# Tag_V1.net
KiCad netlist of a schematic drawn in EAGLE
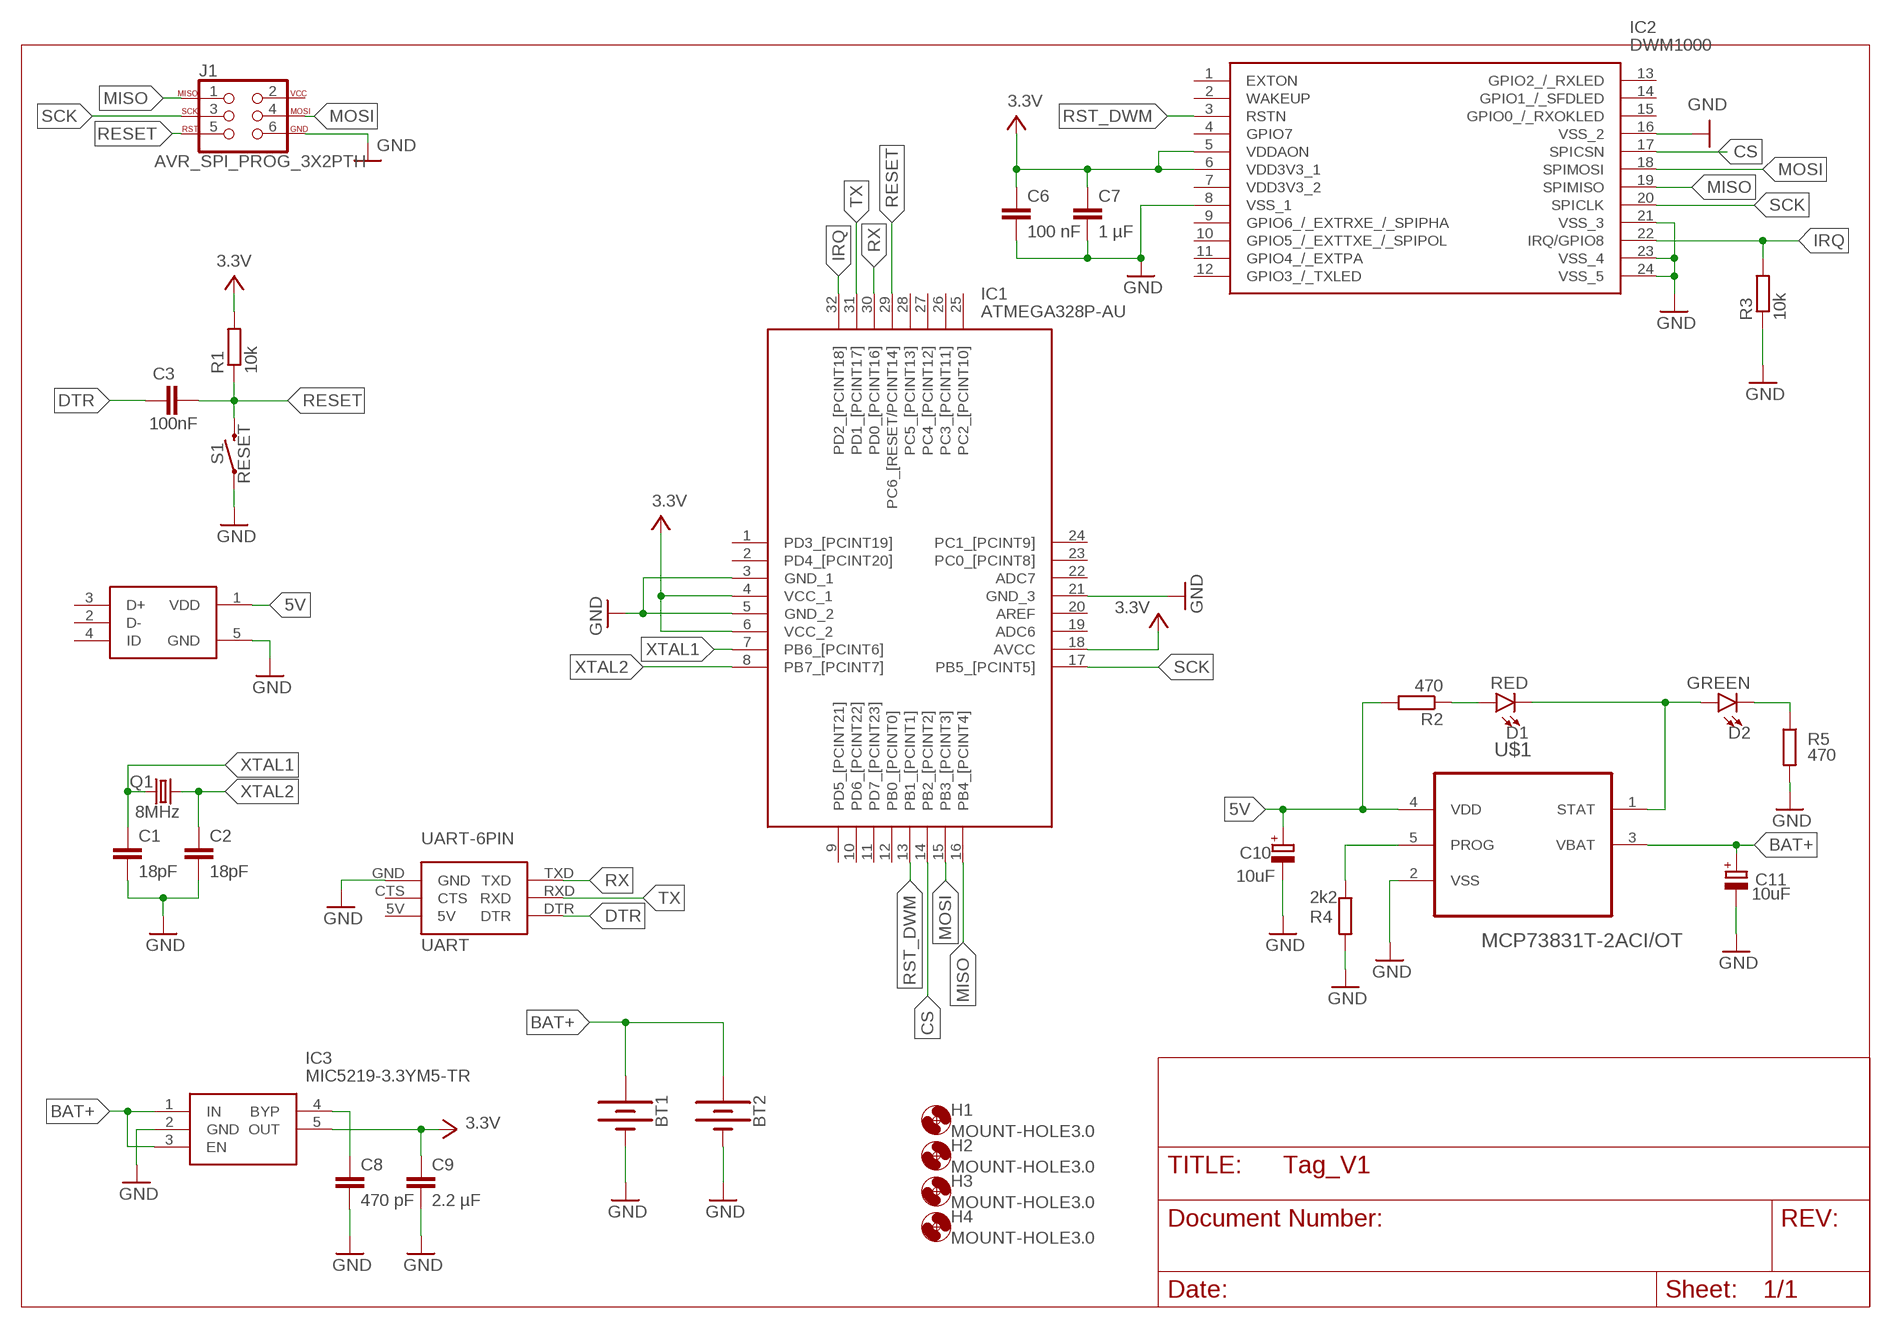
[diagram p0: schematic, sheet 1]

(export (version "E")
  (design (tool "Eeschema 10.0.6"))
  (components
    (comp (ref "BT1")
      (value "BATTERY-18650")
      (footprint "eagle-import:BATTERY_18650-HOLDER")
      (libsource (lib "eagle-import") (part "BATTERY-18650"))
    )
    (comp (ref "BT2")
      (value "BATTERY-18650")
      (footprint "eagle-import:BATTERY_18650-HOLDER")
      (libsource (lib "eagle-import") (part "BATTERY-18650"))
    )
    (comp (ref "C1")
      (value "18pF")
      (footprint "eagle-import:C0805")
      (libsource (lib "eagle-import") (part "C-EUC0805"))
    )
    (comp (ref "C2")
      (value "18pF")
      (footprint "eagle-import:C0805")
      (libsource (lib "eagle-import") (part "C-EUC0805"))
    )
    (comp (ref "C3")
      (value "100nF")
      (footprint "eagle-import:C0805")
      (libsource (lib "eagle-import") (part "C-EUC0805"))
    )
    (comp (ref "C6")
      (value "100 nF")
      (footprint "eagle-import:C0805")
      (libsource (lib "eagle-import") (part "C-EUC0805"))
    )
    (comp (ref "C7")
      (value "1 µF")
      (footprint "eagle-import:C0805")
      (libsource (lib "eagle-import") (part "C-EUC0805"))
    )
    (comp (ref "C8")
      (value "470 pF")
      (footprint "eagle-import:C0805")
      (libsource (lib "eagle-import") (part "C-EUC0805"))
    )
    (comp (ref "C9")
      (value "2.2 µF")
      (footprint "eagle-import:C0805")
      (libsource (lib "eagle-import") (part "C-EUC0805"))
    )
    (comp (ref "C10")
      (value "10uF")
      (footprint "eagle-import:E2,5-7")
      (libsource (lib "eagle-import") (part "CPOL-EUE2.5-7"))
    )
    (comp (ref "C11")
      (value "10uF")
      (footprint "eagle-import:E2,5-7")
      (libsource (lib "eagle-import") (part "CPOL-EUE2.5-7"))
    )
    (comp (ref "D1")
      (value "RED")
      (footprint "eagle-import:LED-1206")
      (libsource (lib "eagle-import") (part "LED-RED1206"))
    )
    (comp (ref "D2")
      (value "GREEN")
      (footprint "eagle-import:LED-1206")
      (libsource (lib "eagle-import") (part "LED-GREEN1206"))
    )
    (comp (ref "H1")
      (value "MOUNT-HOLE3.0")
      (footprint "eagle-import:3,0")
      (libsource (lib "eagle-import") (part "MOUNT-HOLE3.0"))
    )
    (comp (ref "H2")
      (value "MOUNT-HOLE3.0")
      (footprint "eagle-import:3,0")
      (libsource (lib "eagle-import") (part "MOUNT-HOLE3.0"))
    )
    (comp (ref "H3")
      (value "MOUNT-HOLE3.0")
      (footprint "eagle-import:3,0")
      (libsource (lib "eagle-import") (part "MOUNT-HOLE3.0"))
    )
    (comp (ref "H4")
      (value "MOUNT-HOLE3.0")
      (footprint "eagle-import:3,0")
      (libsource (lib "eagle-import") (part "MOUNT-HOLE3.0"))
    )
    (comp (ref "IC1")
      (value "ATMEGA328P-AU")
      (footprint "eagle-import:QFP80P900X900X120-32N")
      (fields (field (name "RS_PART_NUMBER") "1310271"))
      (libsource (lib "eagle-import") (part "ATMEGA328P-AU"))
    )
    (comp (ref "IC2")
      (value "DWM1000")
      (footprint "eagle-import:DWM1000")
      (libsource (lib "eagle-import") (part "DWM1000"))
    )
    (comp (ref "IC3")
      (value "MIC5219-3.3YM5-TR")
      (footprint "eagle-import:SOT95P280X130-5N")
      (fields
        (field (name "MOUSER_PART_NUMBER") "998-MIC5219-3.3YM5TR")
        (field (name "RS_PART_NUMBER") "9101685P")
      )
      (libsource (lib "eagle-import") (part "MIC5219-3.3YM5-TR"))
    )
    (comp (ref "J1")
      (value "AVR_SPI_PROG_3X2PTH")
      (footprint "eagle-import:2X3")
      (libsource (lib "eagle-import") (part "AVR_SPI_PROG_3X2PTH"))
    )
    (comp (ref "Q1")
      (value "8MHz")
      (footprint "eagle-import:HC49UP")
      (libsource (lib "eagle-import") (part "CRYSTALHC49UP"))
    )
    (comp (ref "R1")
      (value "10k")
      (footprint "eagle-import:R0805")
      (libsource (lib "eagle-import") (part "R-EU_R0805"))
    )
    (comp (ref "R2")
      (value "470")
      (footprint "eagle-import:R0805")
      (libsource (lib "eagle-import") (part "R-EU_R0805"))
    )
    (comp (ref "R3")
      (value "10k")
      (footprint "eagle-import:R0805")
      (libsource (lib "eagle-import") (part "R-EU_R0805"))
    )
    (comp (ref "R4")
      (value "2k2")
      (footprint "eagle-import:R0805")
      (libsource (lib "eagle-import") (part "R-EU_R0805"))
    )
    (comp (ref "R5")
      (value "470")
      (footprint "eagle-import:R0805")
      (libsource (lib "eagle-import") (part "R-EU_R0805"))
    )
    (comp (ref "S1")
      (value "RESET")
      (footprint "eagle-import:TACTILE_SWITCH_PTH_6.0MM")
      (libsource (lib "eagle-import") (part "MOMENTARY-SWITCH-SPST-PTH-6.0MM"))
    )
    (comp (ref "U$1")
      (value "MCP73831T-2ACI/OT")
      (footprint "eagle-import:SOT95P280X145-5N")
      (fields (field (name "MF") "Microchip"))
      (libsource (lib "eagle-import") (part "MCP73831T-2ACI/OT"))
    )
    (comp (ref "U$2")
      (value "UART-6PIN")
      (footprint "eagle-import:UART-6PIN")
      (libsource (lib "eagle-import") (part "UART-6PIN"))
    )
    (comp (ref "U1")
      (value "105017-0001")
      (footprint "eagle-import:MOLEX_105017-0001")
      (fields (field (name "MF") "Molex"))
      (libsource (lib "eagle-import") (part "105017-0001"))
    )
  )
  (nets
    (net (code "1") (name "5V") (class "Default")
      (node (ref "C10") (pin "+") (pinfunction "+_+") (pintype "passive"))
      (node (ref "R2") (pin "2") (pinfunction "2_2") (pintype "passive"))
      (node (ref "U$1") (pin "4") (pinfunction "VDD_4") (pintype "power_in"))
      (node (ref "U1") (pin "1") (pinfunction "VDD_1") (pintype "power_in"))
    )
    (net (code "2") (name "BAT+") (class "Default")
      (node (ref "BT1") (pin "PWR@1") (pinfunction "+_PWR@1") (pintype "power_in"))
      (node (ref "BT2") (pin "PWR@1") (pinfunction "+_PWR@1") (pintype "power_in"))
      (node (ref "C11") (pin "+") (pinfunction "+_+") (pintype "passive"))
      (node (ref "IC3") (pin "1") (pinfunction "IN_1") (pintype "bidirectional"))
      (node (ref "IC3") (pin "3") (pinfunction "EN_3") (pintype "bidirectional"))
      (node (ref "U$1") (pin "3") (pinfunction "VBAT_3") (pintype "output"))
    )
    (net (code "3") (name "CS") (class "Default")
      (node (ref "IC1") (pin "14") (pinfunction "PB2_[PCINT2]_14") (pintype "bidirectional"))
      (node (ref "IC2") (pin "17") (pinfunction "SPICSN_17") (pintype "bidirectional"))
    )
    (net (code "4") (name "DTR") (class "Default")
      (node (ref "C3") (pin "1") (pinfunction "1_1") (pintype "passive"))
      (node (ref "U$2") (pin "DTR") (pinfunction "DTR_DTR") (pintype "bidirectional"))
    )
    (net (code "5") (name "GND") (class "Default")
      (node (ref "BT1") (pin "GND@1") (pinfunction "-_GND@1") (pintype "power_in"))
      (node (ref "BT2") (pin "GND@1") (pinfunction "-_GND@1") (pintype "power_in"))
      (node (ref "C1") (pin "2") (pinfunction "2_2") (pintype "passive"))
      (node (ref "C10") (pin "-") (pinfunction "-_-") (pintype "passive"))
      (node (ref "C11") (pin "-") (pinfunction "-_-") (pintype "passive"))
      (node (ref "C2") (pin "2") (pinfunction "2_2") (pintype "passive"))
      (node (ref "C6") (pin "2") (pinfunction "2_2") (pintype "passive"))
      (node (ref "C7") (pin "2") (pinfunction "2_2") (pintype "passive"))
      (node (ref "C8") (pin "2") (pinfunction "2_2") (pintype "passive"))
      (node (ref "C9") (pin "2") (pinfunction "2_2") (pintype "passive"))
      (node (ref "IC1") (pin "21") (pinfunction "GND_3_21") (pintype "power_in"))
      (node (ref "IC1") (pin "3") (pinfunction "GND_1_3") (pintype "power_in"))
      (node (ref "IC1") (pin "5") (pinfunction "GND_2_5") (pintype "power_in"))
      (node (ref "IC2") (pin "16") (pinfunction "VSS_2_16") (pintype "bidirectional"))
      (node (ref "IC2") (pin "21") (pinfunction "VSS_3_21") (pintype "bidirectional"))
      (node (ref "IC2") (pin "23") (pinfunction "VSS_4_23") (pintype "bidirectional"))
      (node (ref "IC2") (pin "24") (pinfunction "VSS_5_24") (pintype "bidirectional"))
      (node (ref "IC2") (pin "8") (pinfunction "VSS_1_8") (pintype "bidirectional"))
      (node (ref "IC3") (pin "2") (pinfunction "GND_2") (pintype "bidirectional"))
      (node (ref "J1") (pin "6") (pinfunction "6_6") (pintype "passive"))
      (node (ref "R3") (pin "1") (pinfunction "1_1") (pintype "passive"))
      (node (ref "R4") (pin "2") (pinfunction "2_2") (pintype "passive"))
      (node (ref "R5") (pin "2") (pinfunction "2_2") (pintype "passive"))
      (node (ref "S1") (pin "1") (pinfunction "1_1") (pintype "passive"))
      (node (ref "U$1") (pin "2") (pinfunction "VSS_2") (pintype "power_in"))
      (node (ref "U$2") (pin "GND") (pinfunction "GND_GND") (pintype "bidirectional"))
      (node (ref "U1") (pin "5") (pinfunction "GND_5") (pintype "power_in"))
    )
    (net (code "6") (name "IRQ") (class "Default")
      (node (ref "IC1") (pin "32") (pinfunction "PD2_[PCINT18]_32") (pintype "bidirectional"))
      (node (ref "IC2") (pin "22") (pinfunction "IRQ/GPIO8_22") (pintype "bidirectional"))
      (node (ref "R3") (pin "2") (pinfunction "2_2") (pintype "passive"))
    )
    (net (code "7") (name "MISO") (class "Default")
      (node (ref "IC1") (pin "16") (pinfunction "PB4_[PCINT4]_16") (pintype "bidirectional"))
      (node (ref "IC2") (pin "19") (pinfunction "SPIMISO_19") (pintype "bidirectional"))
      (node (ref "J1") (pin "1") (pinfunction "1_1") (pintype "passive"))
    )
    (net (code "8") (name "MOSI") (class "Default")
      (node (ref "IC1") (pin "15") (pinfunction "PB3_[PCINT3]_15") (pintype "bidirectional"))
      (node (ref "IC2") (pin "18") (pinfunction "SPIMOSI_18") (pintype "bidirectional"))
      (node (ref "J1") (pin "4") (pinfunction "4_4") (pintype "passive"))
    )
    (net (code "9") (name "Net-(D1-PadA)") (class "Default")
      (node (ref "D1") (pin "A") (pinfunction "A_A") (pintype "passive"))
      (node (ref "R2") (pin "1") (pinfunction "1_1") (pintype "passive"))
    )
    (net (code "10") (name "Net-(D2-PadC)") (class "Default")
      (node (ref "D2") (pin "C") (pinfunction "C_C") (pintype "passive"))
      (node (ref "R5") (pin "1") (pinfunction "1_1") (pintype "passive"))
    )
    (net (code "11") (name "Net-(IC3-BYP)") (class "Default")
      (node (ref "C8") (pin "1") (pinfunction "1_1") (pintype "passive"))
      (node (ref "IC3") (pin "4") (pinfunction "BYP_4") (pintype "bidirectional"))
    )
    (net (code "12") (name "Net-(U$1-PROG)") (class "Default")
      (node (ref "R4") (pin "1") (pinfunction "1_1") (pintype "passive"))
      (node (ref "U$1") (pin "5") (pinfunction "PROG_5") (pintype "input"))
    )
    (net (code "13") (name "Net-(U$1-STAT)") (class "Default")
      (node (ref "D1") (pin "C") (pinfunction "C_C") (pintype "passive"))
      (node (ref "D2") (pin "A") (pinfunction "A_A") (pintype "passive"))
      (node (ref "U$1") (pin "1") (pinfunction "STAT_1") (pintype "output"))
    )
    (net (code "14") (name "RESET") (class "Default")
      (node (ref "C3") (pin "2") (pinfunction "2_2") (pintype "passive"))
      (node (ref "IC1") (pin "29") (pinfunction "PC6_[RESET/PCINT14]_29") (pintype "bidirectional"))
      (node (ref "J1") (pin "5") (pinfunction "5_5") (pintype "passive"))
      (node (ref "R1") (pin "1") (pinfunction "1_1") (pintype "passive"))
      (node (ref "S1") (pin "3") (pinfunction "2_3") (pintype "passive"))
    )
    (net (code "15") (name "RST_DWM") (class "Default")
      (node (ref "IC1") (pin "13") (pinfunction "PB1_[PCINT1]_13") (pintype "bidirectional"))
      (node (ref "IC2") (pin "3") (pinfunction "RSTN_3") (pintype "bidirectional"))
    )
    (net (code "16") (name "RX") (class "Default")
      (node (ref "IC1") (pin "30") (pinfunction "PD0_[PCINT16]_30") (pintype "bidirectional"))
      (node (ref "U$2") (pin "TXD") (pinfunction "TXD_TXD") (pintype "bidirectional"))
    )
    (net (code "17") (name "SCK") (class "Default")
      (node (ref "IC1") (pin "17") (pinfunction "PB5_[PCINT5]_17") (pintype "bidirectional"))
      (node (ref "IC2") (pin "20") (pinfunction "SPICLK_20") (pintype "bidirectional"))
      (node (ref "J1") (pin "3") (pinfunction "3_3") (pintype "passive"))
    )
    (net (code "18") (name "TX") (class "Default")
      (node (ref "IC1") (pin "31") (pinfunction "PD1_[PCINT17]_31") (pintype "bidirectional"))
      (node (ref "U$2") (pin "RXD") (pinfunction "RXD_RXD") (pintype "bidirectional"))
    )
    (net (code "19") (name "VCC") (class "Default")
      (node (ref "C6") (pin "1") (pinfunction "1_1") (pintype "passive"))
      (node (ref "C7") (pin "1") (pinfunction "1_1") (pintype "passive"))
      (node (ref "C9") (pin "1") (pinfunction "1_1") (pintype "passive"))
      (node (ref "IC1") (pin "18") (pinfunction "AVCC_18") (pintype "power_in"))
      (node (ref "IC1") (pin "4") (pinfunction "VCC_1_4") (pintype "power_in"))
      (node (ref "IC1") (pin "6") (pinfunction "VCC_2_6") (pintype "power_in"))
      (node (ref "IC2") (pin "5") (pinfunction "VDDAON_5") (pintype "bidirectional"))
      (node (ref "IC2") (pin "6") (pinfunction "VDD3V3_1_6") (pintype "bidirectional"))
      (node (ref "IC3") (pin "5") (pinfunction "OUT_5") (pintype "bidirectional"))
      (node (ref "R1") (pin "2") (pinfunction "2_2") (pintype "passive"))
    )
    (net (code "20") (name "XTAL1") (class "Default")
      (node (ref "C1") (pin "1") (pinfunction "1_1") (pintype "passive"))
      (node (ref "IC1") (pin "7") (pinfunction "PB6_[PCINT6]_7") (pintype "bidirectional"))
      (node (ref "Q1") (pin "1") (pinfunction "1_1") (pintype "passive"))
    )
    (net (code "21") (name "XTAL2") (class "Default")
      (node (ref "C2") (pin "1") (pinfunction "1_1") (pintype "passive"))
      (node (ref "IC1") (pin "8") (pinfunction "PB7_[PCINT7]_8") (pintype "bidirectional"))
      (node (ref "Q1") (pin "2") (pinfunction "2_2") (pintype "passive"))
    )
    (net (code "22") (name "unconnected-(IC1-ADC6-Pad19)") (class "Default")
      (node (ref "IC1") (pin "19") (pinfunction "ADC6_19") (pintype "bidirectional"))
    )
    (net (code "23") (name "unconnected-(IC1-ADC7-Pad22)") (class "Default")
      (node (ref "IC1") (pin "22") (pinfunction "ADC7_22") (pintype "bidirectional"))
    )
    (net (code "24") (name "unconnected-(IC1-AREF-Pad20)") (class "Default")
      (node (ref "IC1") (pin "20") (pinfunction "AREF_20") (pintype "bidirectional"))
    )
    (net (code "25") (name "unconnected-(IC1-PB0_[PCINT0]-Pad12)") (class "Default")
      (node (ref "IC1") (pin "12") (pinfunction "PB0_[PCINT0]_12") (pintype "bidirectional"))
    )
    (net (code "26") (name "unconnected-(IC1-PC0_[PCINT8]-Pad23)") (class "Default")
      (node (ref "IC1") (pin "23") (pinfunction "PC0_[PCINT8]_23") (pintype "bidirectional"))
    )
    (net (code "27") (name "unconnected-(IC1-PC1_[PCINT9]-Pad24)") (class "Default")
      (node (ref "IC1") (pin "24") (pinfunction "PC1_[PCINT9]_24") (pintype "bidirectional"))
    )
    (net (code "28") (name "unconnected-(IC1-PC2_[PCINT10]-Pad25)") (class "Default")
      (node (ref "IC1") (pin "25") (pinfunction "PC2_[PCINT10]_25") (pintype "bidirectional"))
    )
    (net (code "29") (name "unconnected-(IC1-PC3_[PCINT11]-Pad26)") (class "Default")
      (node (ref "IC1") (pin "26") (pinfunction "PC3_[PCINT11]_26") (pintype "bidirectional"))
    )
    (net (code "30") (name "unconnected-(IC1-PC4_[PCINT12]-Pad27)") (class "Default")
      (node (ref "IC1") (pin "27") (pinfunction "PC4_[PCINT12]_27") (pintype "bidirectional"))
    )
    (net (code "31") (name "unconnected-(IC1-PC5_[PCINT13]-Pad28)") (class "Default")
      (node (ref "IC1") (pin "28") (pinfunction "PC5_[PCINT13]_28") (pintype "bidirectional"))
    )
    (net (code "32") (name "unconnected-(IC1-PD3_[PCINT19]-Pad1)") (class "Default")
      (node (ref "IC1") (pin "1") (pinfunction "PD3_[PCINT19]_1") (pintype "bidirectional"))
    )
    (net (code "33") (name "unconnected-(IC1-PD4_[PCINT20]-Pad2)") (class "Default")
      (node (ref "IC1") (pin "2") (pinfunction "PD4_[PCINT20]_2") (pintype "bidirectional"))
    )
    (net (code "34") (name "unconnected-(IC1-PD5_[PCINT21]-Pad9)") (class "Default")
      (node (ref "IC1") (pin "9") (pinfunction "PD5_[PCINT21]_9") (pintype "bidirectional"))
    )
    (net (code "35") (name "unconnected-(IC1-PD6_[PCINT22]-Pad10)") (class "Default")
      (node (ref "IC1") (pin "10") (pinfunction "PD6_[PCINT22]_10") (pintype "bidirectional"))
    )
    (net (code "36") (name "unconnected-(IC1-PD7_[PCINT23]-Pad11)") (class "Default")
      (node (ref "IC1") (pin "11") (pinfunction "PD7_[PCINT23]_11") (pintype "bidirectional"))
    )
    (net (code "37") (name "unconnected-(IC2-EXTON-Pad1)") (class "Default")
      (node (ref "IC2") (pin "1") (pinfunction "EXTON_1") (pintype "bidirectional"))
    )
    (net (code "38") (name "unconnected-(IC2-GPIO0_{slash}_RXOKLED-Pad15)") (class "Default")
      (node (ref "IC2") (pin "15") (pinfunction "GPIO0_/_RXOKLED_15") (pintype "bidirectional"))
    )
    (net (code "39") (name "unconnected-(IC2-GPIO1_{slash}_SFDLED-Pad14)") (class "Default")
      (node (ref "IC2") (pin "14") (pinfunction "GPIO1_/_SFDLED_14") (pintype "bidirectional"))
    )
    (net (code "40") (name "unconnected-(IC2-GPIO2_{slash}_RXLED-Pad13)") (class "Default")
      (node (ref "IC2") (pin "13") (pinfunction "GPIO2_/_RXLED_13") (pintype "bidirectional"))
    )
    (net (code "41") (name "unconnected-(IC2-GPIO3_{slash}_TXLED-Pad12)") (class "Default")
      (node (ref "IC2") (pin "12") (pinfunction "GPIO3_/_TXLED_12") (pintype "bidirectional"))
    )
    (net (code "42") (name "unconnected-(IC2-GPIO4_{slash}_EXTPA-Pad11)") (class "Default")
      (node (ref "IC2") (pin "11") (pinfunction "GPIO4_/_EXTPA_11") (pintype "bidirectional"))
    )
    (net (code "43") (name "unconnected-(IC2-GPIO5_{slash}_EXTTXE_{slash}_SPIPOL-Pad10)") (class "Default")
      (node (ref "IC2") (pin "10") (pinfunction "GPIO5_/_EXTTXE_/_SPIPOL_10") (pintype "bidirectional"))
    )
    (net (code "44") (name "unconnected-(IC2-GPIO6_{slash}_EXTRXE_{slash}_SPIPHA-Pad9)") (class "Default")
      (node (ref "IC2") (pin "9") (pinfunction "GPIO6_/_EXTRXE_/_SPIPHA_9") (pintype "bidirectional"))
    )
    (net (code "45") (name "unconnected-(IC2-GPIO7-Pad4)") (class "Default")
      (node (ref "IC2") (pin "4") (pinfunction "GPIO7_4") (pintype "bidirectional"))
    )
    (net (code "46") (name "unconnected-(IC2-VDD3V3_2-Pad7)") (class "Default")
      (node (ref "IC2") (pin "7") (pinfunction "VDD3V3_2_7") (pintype "bidirectional"))
    )
    (net (code "47") (name "unconnected-(IC2-WAKEUP-Pad2)") (class "Default")
      (node (ref "IC2") (pin "2") (pinfunction "WAKEUP_2") (pintype "bidirectional"))
    )
    (net (code "48") (name "unconnected-(J1-Pad2)") (class "Default")
      (node (ref "J1") (pin "2") (pinfunction "2_2") (pintype "passive"))
    )
    (net (code "49") (name "unconnected-(U$2-Pad5V)") (class "Default")
      (node (ref "U$2") (pin "5V") (pinfunction "5V_5V") (pintype "bidirectional"))
    )
    (net (code "50") (name "unconnected-(U$2-PadCTS)") (class "Default")
      (node (ref "U$2") (pin "CTS") (pinfunction "CTS_CTS") (pintype "bidirectional"))
    )
    (net (code "51") (name "unconnected-(U1-D+-Pad3)") (class "Default")
      (node (ref "U1") (pin "3") (pinfunction "D+_3") (pintype "bidirectional"))
    )
    (net (code "52") (name "unconnected-(U1-D--Pad2)") (class "Default")
      (node (ref "U1") (pin "2") (pinfunction "D-_2") (pintype "bidirectional"))
    )
    (net (code "53") (name "unconnected-(U1-ID-Pad4)") (class "Default")
      (node (ref "U1") (pin "4") (pinfunction "ID_4") (pintype "passive"))
    )
  )
)
